# AetherMesh_Test_Fixture_LGA_V1_0.net
KiCad netlist of a schematic drawn in EAGLE
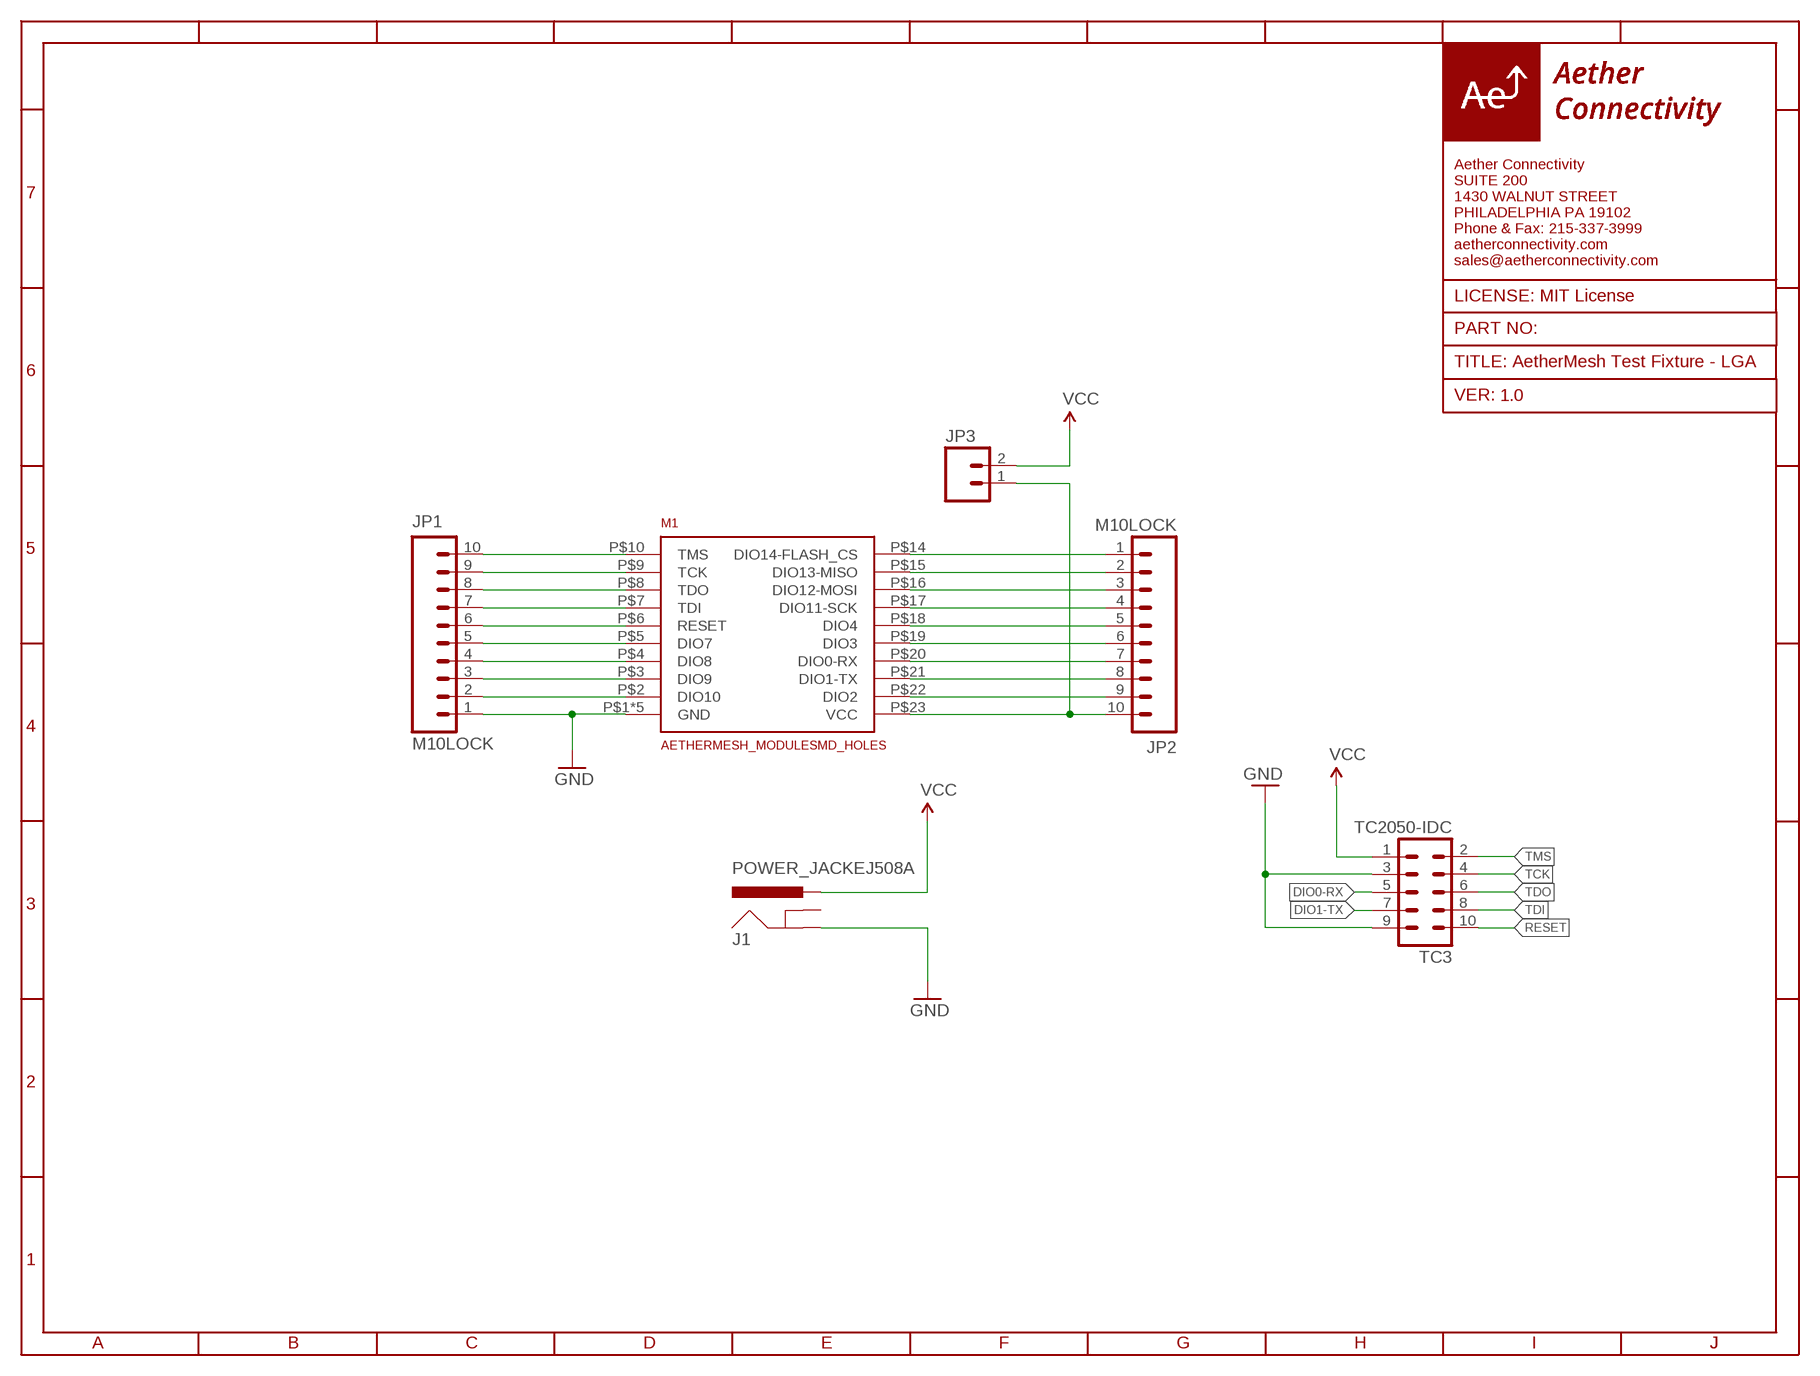
[diagram p0: schematic, sheet 1]

(export (version "E")
  (design (tool "Eeschema 10.0.6"))
  (components
    (comp (ref "J1")
      (value "POWER_JACKEJ508A")
      (footprint "eagle-import:DC_JACK_EJ508A")
      (libsource (lib "eagle-import") (part "POWER_JACKEJ508A"))
    )
    (comp (ref "JP1")
      (value "M10LOCK")
      (footprint "eagle-import:1X10_LOCK")
      (libsource (lib "eagle-import") (part "M10LOCK"))
    )
    (comp (ref "JP2")
      (value "M10LOCK")
      (footprint "eagle-import:1X10_LOCK")
      (libsource (lib "eagle-import") (part "M10LOCK"))
    )
    (comp (ref "JP3")
      (value "M02LOCK")
      (footprint "eagle-import:1X02_LOCK")
      (libsource (lib "eagle-import") (part "M02LOCK"))
    )
    (comp (ref "M1")
      (value "AETHERMESH_MODULESMD_HOLES")
      (footprint "eagle-import:AETHERMESH_SMD_MOUNT_HOLES")
      (libsource (lib "eagle-import") (part "AETHERMESH_MODULESMD_HOLES"))
    )
    (comp (ref "TC3")
      (value "TC2050-IDC")
      (footprint "eagle-import:TC2050-IDC")
      (libsource (lib "eagle-import") (part "TC2050-IDC"))
    )
  )
  (nets
    (net (code "1") (name "DIO0-RX") (class "Default")
      (node (ref "JP2") (pin "7") (pinfunction "7_7") (pintype "passive"))
      (node (ref "M1") (pin "P$20") (pinfunction "DIO0-RX_P$20") (pintype "bidirectional"))
      (node (ref "TC3") (pin "5") (pinfunction "5_5") (pintype "passive"))
    )
    (net (code "2") (name "DIO1-TX") (class "Default")
      (node (ref "JP2") (pin "8") (pinfunction "8_8") (pintype "passive"))
      (node (ref "M1") (pin "P$21") (pinfunction "DIO1-TX_P$21") (pintype "bidirectional"))
      (node (ref "TC3") (pin "7") (pinfunction "7_7") (pintype "passive"))
    )
    (net (code "3") (name "GND") (class "Default")
      (node (ref "J1") (pin "1") (pinfunction "GND_1") (pintype "bidirectional"))
      (node (ref "JP1") (pin "1") (pinfunction "1_1") (pintype "passive"))
      (node (ref "M1") (pin "P$1") (pinfunction "GND_P$1") (pintype "bidirectional"))
      (node (ref "M1") (pin "P$11") (pinfunction "GND_P$11") (pintype "bidirectional"))
      (node (ref "M1") (pin "P$12") (pinfunction "GND_P$12") (pintype "bidirectional"))
      (node (ref "M1") (pin "P$13") (pinfunction "GND_P$13") (pintype "bidirectional"))
      (node (ref "M1") (pin "P$24") (pinfunction "GND_P$24") (pintype "bidirectional"))
      (node (ref "TC3") (pin "3") (pinfunction "3_3") (pintype "passive"))
      (node (ref "TC3") (pin "9") (pinfunction "9_9") (pintype "passive"))
    )
    (net (code "4") (name "Net-(M1-DIO2)") (class "Default")
      (node (ref "JP2") (pin "9") (pinfunction "9_9") (pintype "passive"))
      (node (ref "M1") (pin "P$22") (pinfunction "DIO2_P$22") (pintype "bidirectional"))
    )
    (net (code "5") (name "Net-(M1-DIO3)") (class "Default")
      (node (ref "JP2") (pin "6") (pinfunction "6_6") (pintype "passive"))
      (node (ref "M1") (pin "P$19") (pinfunction "DIO3_P$19") (pintype "bidirectional"))
    )
    (net (code "6") (name "Net-(M1-DIO4)") (class "Default")
      (node (ref "JP2") (pin "5") (pinfunction "5_5") (pintype "passive"))
      (node (ref "M1") (pin "P$18") (pinfunction "DIO4_P$18") (pintype "bidirectional"))
    )
    (net (code "7") (name "Net-(M1-DIO7)") (class "Default")
      (node (ref "JP1") (pin "5") (pinfunction "5_5") (pintype "passive"))
      (node (ref "M1") (pin "P$5") (pinfunction "DIO7_P$5") (pintype "bidirectional"))
    )
    (net (code "8") (name "Net-(M1-DIO8)") (class "Default")
      (node (ref "JP1") (pin "4") (pinfunction "4_4") (pintype "passive"))
      (node (ref "M1") (pin "P$4") (pinfunction "DIO8_P$4") (pintype "bidirectional"))
    )
    (net (code "9") (name "Net-(M1-DIO9)") (class "Default")
      (node (ref "JP1") (pin "3") (pinfunction "3_3") (pintype "passive"))
      (node (ref "M1") (pin "P$3") (pinfunction "DIO9_P$3") (pintype "bidirectional"))
    )
    (net (code "10") (name "Net-(M1-DIO10)") (class "Default")
      (node (ref "JP1") (pin "2") (pinfunction "2_2") (pintype "passive"))
      (node (ref "M1") (pin "P$2") (pinfunction "DIO10_P$2") (pintype "bidirectional"))
    )
    (net (code "11") (name "Net-(M1-DIO11-SCK)") (class "Default")
      (node (ref "JP2") (pin "4") (pinfunction "4_4") (pintype "passive"))
      (node (ref "M1") (pin "P$17") (pinfunction "DIO11-SCK_P$17") (pintype "bidirectional"))
    )
    (net (code "12") (name "Net-(M1-DIO12-MOSI)") (class "Default")
      (node (ref "JP2") (pin "3") (pinfunction "3_3") (pintype "passive"))
      (node (ref "M1") (pin "P$16") (pinfunction "DIO12-MOSI_P$16") (pintype "bidirectional"))
    )
    (net (code "13") (name "Net-(M1-DIO13-MISO)") (class "Default")
      (node (ref "JP2") (pin "2") (pinfunction "2_2") (pintype "passive"))
      (node (ref "M1") (pin "P$15") (pinfunction "DIO13-MISO_P$15") (pintype "bidirectional"))
    )
    (net (code "14") (name "Net-(M1-DIO14-FLASH_CS)") (class "Default")
      (node (ref "JP2") (pin "1") (pinfunction "1_1") (pintype "passive"))
      (node (ref "M1") (pin "P$14") (pinfunction "DIO14-FLASH_CS_P$14") (pintype "bidirectional"))
    )
    (net (code "15") (name "Net-(M1-VCC)") (class "Default")
      (node (ref "JP2") (pin "10") (pinfunction "10_10") (pintype "passive"))
      (node (ref "JP3") (pin "1") (pinfunction "1_1") (pintype "passive"))
      (node (ref "M1") (pin "P$23") (pinfunction "VCC_P$23") (pintype "bidirectional"))
    )
    (net (code "16") (name "RESET") (class "Default")
      (node (ref "JP1") (pin "6") (pinfunction "6_6") (pintype "passive"))
      (node (ref "M1") (pin "P$6") (pinfunction "RESET_P$6") (pintype "bidirectional"))
      (node (ref "TC3") (pin "10") (pinfunction "10_10") (pintype "passive"))
    )
    (net (code "17") (name "TCK") (class "Default")
      (node (ref "JP1") (pin "9") (pinfunction "9_9") (pintype "passive"))
      (node (ref "M1") (pin "P$9") (pinfunction "TCK_P$9") (pintype "bidirectional"))
      (node (ref "TC3") (pin "4") (pinfunction "4_4") (pintype "passive"))
    )
    (net (code "18") (name "TDI") (class "Default")
      (node (ref "JP1") (pin "7") (pinfunction "7_7") (pintype "passive"))
      (node (ref "M1") (pin "P$7") (pinfunction "TDI_P$7") (pintype "bidirectional"))
      (node (ref "TC3") (pin "8") (pinfunction "8_8") (pintype "passive"))
    )
    (net (code "19") (name "TDO") (class "Default")
      (node (ref "JP1") (pin "8") (pinfunction "8_8") (pintype "passive"))
      (node (ref "M1") (pin "P$8") (pinfunction "TDO_P$8") (pintype "bidirectional"))
      (node (ref "TC3") (pin "6") (pinfunction "6_6") (pintype "passive"))
    )
    (net (code "20") (name "TMS") (class "Default")
      (node (ref "JP1") (pin "10") (pinfunction "10_10") (pintype "passive"))
      (node (ref "M1") (pin "P$10") (pinfunction "TMS_P$10") (pintype "bidirectional"))
      (node (ref "TC3") (pin "2") (pinfunction "2_2") (pintype "passive"))
    )
    (net (code "21") (name "VCC") (class "Default")
      (node (ref "J1") (pin "3") (pinfunction "PWR_3") (pintype "bidirectional"))
      (node (ref "JP3") (pin "2") (pinfunction "2_2") (pintype "passive"))
      (node (ref "TC3") (pin "1") (pinfunction "1_1") (pintype "passive"))
    )
    (net (code "22") (name "unconnected-(J1-GNDBREAK-Pad2)") (class "Default")
      (node (ref "J1") (pin "2") (pinfunction "GNDBREAK_2") (pintype "bidirectional"))
    )
  )
)
